# Sensor.net
KiCad netlist of a schematic drawn in Altium Designer
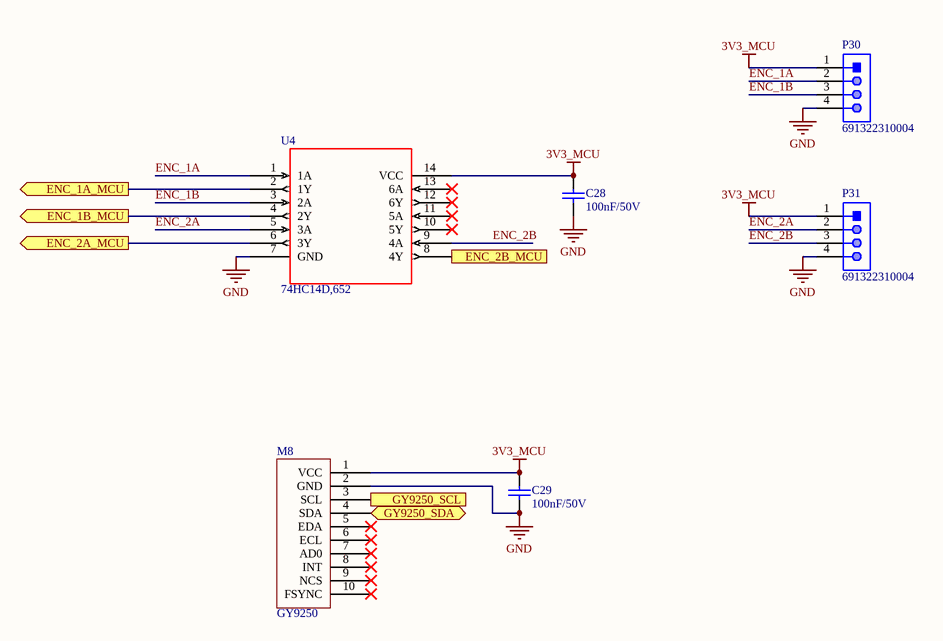
[diagram p0: Sensor.SchDoc]

(export (version "E")
  (design (tool "Eeschema 10.0.6"))
  (components
    (comp (ref "C28")
      (value "100nF/50V")
      (footprint "CAP-SM-0805")
      (description "CAP CER 0.1UF 50V Y5V 0805")
      (fields
        (field (name "MANUFACTURER") "Samsung Electro-Mechanics")
        (field (name "MANUFACTURER PART NUMBER") "CL21F104ZBCNNNC")
      )
      (libsource (lib "Capacitor") (part "Cap-100nF-50V-0805"))
    )
    (comp (ref "C29")
      (value "100nF/50V")
      (footprint "CAP-SM-0805")
      (description "CAP CER 0.1UF 50V Y5V 0805")
      (fields
        (field (name "MANUFACTURER") "Samsung Electro-Mechanics")
        (field (name "MANUFACTURER PART NUMBER") "CL21F104ZBCNNNC")
      )
      (libsource (lib "Capacitor") (part "Cap-100nF-50V-0805"))
    )
    (comp (ref "M8") (value "GY9250") (footprint "GY9250") (libsource (lib "chicken") (part "GY9250")))
    (comp (ref "P30")
      (value "691322310004")
      (footprint "691322310004")
      (description "WR-TBL Serie 322 Horizontal PCB Header, Pluggable, pitch 3.81mm, 4p")
      (fields (field (name "PUBLISHER") "Wurth Elektronik"))
      (libsource (lib "o162719v243 Altium_WR-TBL (rev19a)") (part "691322310004"))
    )
    (comp (ref "P31")
      (value "691322310004")
      (footprint "691322310004")
      (description "WR-TBL Serie 322 Horizontal PCB Header, Pluggable, pitch 3.81mm, 4p")
      (fields (field (name "PUBLISHER") "Wurth Elektronik"))
      (libsource (lib "o162719v243 Altium_WR-TBL (rev19a)") (part "691322310004"))
    )
    (comp (ref "U4")
      (value "74HC14D,652")
      (footprint "74HC14D,652")
      (description "No Description Available")
      (fields (field (name "COPYRIGHT") "Copyright (C) 2016 Accelerated Designs. All rights reserved"))
      (libsource (lib "chicken") (part "74HC14D,652"))
    )
  )
  (nets
    (net (code "1") (name "/ENC_1A") (class "Default")
      (node (ref "P30") (pin "2") (pinfunction "2_2") (pintype "passive"))
      (node (ref "U4") (pin "1") (pinfunction "1A_1") (pintype "input"))
    )
    (net (code "2") (name "/ENC_1A_MCU") (class "Default")
      (node (ref "U4") (pin "2") (pinfunction "1Y_2") (pintype "output"))
    )
    (net (code "3") (name "/ENC_1B") (class "Default")
      (node (ref "P30") (pin "3") (pinfunction "3_3") (pintype "passive"))
      (node (ref "U4") (pin "3") (pinfunction "2A_3") (pintype "input"))
    )
    (net (code "4") (name "/ENC_1B_MCU") (class "Default")
      (node (ref "U4") (pin "4") (pinfunction "2Y_4") (pintype "output"))
    )
    (net (code "5") (name "/ENC_2A") (class "Default")
      (node (ref "P31") (pin "2") (pinfunction "2_2") (pintype "passive"))
      (node (ref "U4") (pin "5") (pinfunction "3A_5") (pintype "input"))
    )
    (net (code "6") (name "/ENC_2A_MCU") (class "Default")
      (node (ref "U4") (pin "6") (pinfunction "3Y_6") (pintype "output"))
    )
    (net (code "7") (name "/ENC_2B") (class "Default")
      (node (ref "P31") (pin "3") (pinfunction "3_3") (pintype "passive"))
      (node (ref "U4") (pin "9") (pinfunction "4A_9") (pintype "input"))
    )
    (net (code "8") (name "/ENC_2B_MCU") (class "Default")
      (node (ref "U4") (pin "8") (pinfunction "4Y_8") (pintype "output"))
    )
    (net (code "9") (name "/GY9250_SCL") (class "Default")
      (node (ref "M8") (pin "3") (pinfunction "SCL_3") (pintype "passive"))
    )
    (net (code "10") (name "/GY9250_SDA") (class "Default")
      (node (ref "M8") (pin "4") (pinfunction "SDA_4") (pintype "passive"))
    )
    (net (code "11") (name "3V3_MCU") (class "Default")
      (node (ref "C28") (pin "2") (pinfunction "2_2") (pintype "passive"))
      (node (ref "C29") (pin "2") (pinfunction "2_2") (pintype "passive"))
      (node (ref "M8") (pin "1") (pinfunction "VCC_1") (pintype "passive"))
      (node (ref "P30") (pin "1") (pinfunction "1_1") (pintype "passive"))
      (node (ref "P31") (pin "1") (pinfunction "1_1") (pintype "passive"))
      (node (ref "U4") (pin "14") (pinfunction "VCC_14") (pintype "power_in"))
    )
    (net (code "12") (name "GND") (class "Default")
      (node (ref "C28") (pin "1") (pinfunction "1_1") (pintype "passive"))
      (node (ref "C29") (pin "1") (pinfunction "1_1") (pintype "passive"))
      (node (ref "M8") (pin "2") (pinfunction "GND_2") (pintype "passive"))
      (node (ref "P30") (pin "4") (pinfunction "4_4") (pintype "passive"))
      (node (ref "P31") (pin "4") (pinfunction "4_4") (pintype "passive"))
      (node (ref "U4") (pin "7") (pinfunction "GND_7") (pintype "power_in"))
    )
    (net (code "13") (name "unconnected-(M8-AD0-Pad7)") (class "Default")
      (node (ref "M8") (pin "7") (pinfunction "AD0_7") (pintype "passive+no_connect"))
    )
    (net (code "14") (name "unconnected-(M8-ECL-Pad6)") (class "Default")
      (node (ref "M8") (pin "6") (pinfunction "ECL_6") (pintype "passive+no_connect"))
    )
    (net (code "15") (name "unconnected-(M8-EDA-Pad5)") (class "Default")
      (node (ref "M8") (pin "5") (pinfunction "EDA_5") (pintype "passive+no_connect"))
    )
    (net (code "16") (name "unconnected-(M8-FSYNC-Pad10)") (class "Default")
      (node (ref "M8") (pin "10") (pinfunction "FSYNC_10") (pintype "passive+no_connect"))
    )
    (net (code "17") (name "unconnected-(M8-INT-Pad8)") (class "Default")
      (node (ref "M8") (pin "8") (pinfunction "INT_8") (pintype "passive+no_connect"))
    )
    (net (code "18") (name "unconnected-(M8-NCS-Pad9)") (class "Default")
      (node (ref "M8") (pin "9") (pinfunction "NCS_9") (pintype "passive+no_connect"))
    )
    (net (code "19") (name "unconnected-(U4-5A-Pad11)") (class "Default")
      (node (ref "U4") (pin "11") (pinfunction "5A_11") (pintype "input+no_connect"))
    )
    (net (code "20") (name "unconnected-(U4-5Y-Pad10)") (class "Default")
      (node (ref "U4") (pin "10") (pinfunction "5Y_10") (pintype "output+no_connect"))
    )
    (net (code "21") (name "unconnected-(U4-6A-Pad13)") (class "Default")
      (node (ref "U4") (pin "13") (pinfunction "6A_13") (pintype "input+no_connect"))
    )
    (net (code "22") (name "unconnected-(U4-6Y-Pad12)") (class "Default")
      (node (ref "U4") (pin "12") (pinfunction "6Y_12") (pintype "output+no_connect"))
    )
  )
)
